# 5G8_fpv_tx.net
KiCad netlist of a schematic drawn in EAGLE
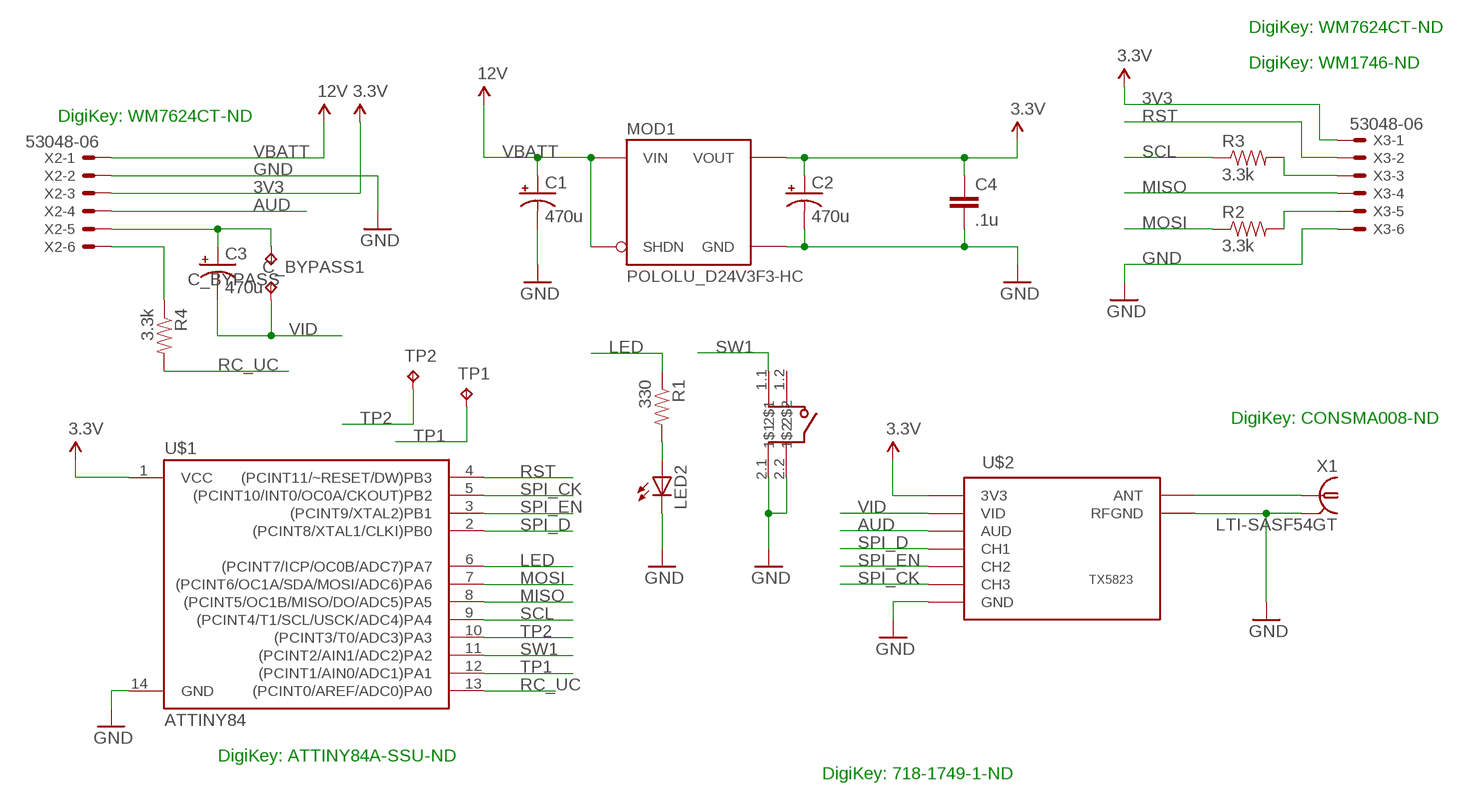
[diagram p0: schematic, sheet 1]

(export (version "E")
  (design (tool "Eeschema 10.0.6"))
  (components
    (comp (ref "C1")
      (value "470u")
      (footprint "eagle-import:VISHAY_D")
      (libsource (lib "eagle-import") (part "VISHAY_D"))
    )
    (comp (ref "C2")
      (value "470u")
      (footprint "eagle-import:VISHAY_D")
      (libsource (lib "eagle-import") (part "VISHAY_D"))
    )
    (comp (ref "C3")
      (value "470u")
      (footprint "eagle-import:VISHAY_D")
      (libsource (lib "eagle-import") (part "VISHAY_D"))
    )
    (comp (ref "C4")
      (value ".1u")
      (footprint "eagle-import:0805")
      (libsource (lib "eagle-import") (part "CAP0805"))
    )
    (comp (ref "C_BYPASS")
      (value "TPTP06SQ")
      (footprint "eagle-import:TP06SQ")
      (libsource (lib "eagle-import") (part "TPTP06SQ"))
    )
    (comp (ref "C_BYPASS1")
      (value "TPTP06SQ")
      (footprint "eagle-import:TP06SQ")
      (libsource (lib "eagle-import") (part "TPTP06SQ"))
    )
    (comp (ref "LED2")
      (value "LEDCHIPLED_0805")
      (footprint "eagle-import:CHIPLED_0805")
      (libsource (lib "eagle-import") (part "LEDCHIPLED_0805"))
    )
    (comp (ref "MOD1")
      (value "POLOLU_D24V3F3-HC")
      (footprint "eagle-import:POLOLU_D24V3F_HC")
      (libsource (lib "eagle-import") (part "POLOLU_D24V3F-HC3"))
    )
    (comp (ref "R1")
      (value "330")
      (footprint "eagle-import:0805")
      (libsource (lib "eagle-import") (part "RESISTOR0805-RES"))
    )
    (comp (ref "R2")
      (value "3.3k")
      (footprint "eagle-import:0805")
      (libsource (lib "eagle-import") (part "RESISTOR0805-RES"))
    )
    (comp (ref "R3")
      (value "3.3k")
      (footprint "eagle-import:0805")
      (libsource (lib "eagle-import") (part "RESISTOR0805-RES"))
    )
    (comp (ref "R4")
      (value "3.3k")
      (footprint "eagle-import:0805")
      (libsource (lib "eagle-import") (part "RESISTOR0805-RES"))
    )
    (comp (ref "TP1")
      (value "TPTP20SQ")
      (footprint "eagle-import:TP20SQ")
      (libsource (lib "eagle-import") (part "TPTP20SQ"))
    )
    (comp (ref "TP2")
      (value "TPTP20SQ")
      (footprint "eagle-import:TP20SQ")
      (libsource (lib "eagle-import") (part "TPTP20SQ"))
    )
    (comp (ref "U$1")
      (value "ATTINY84")
      (footprint "eagle-import:SO14")
      (libsource (lib "eagle-import") (part "ATTINY84"))
    )
    (comp (ref "U$2")
      (value "TX5823")
      (footprint "eagle-import:TX5823")
      (libsource (lib "eagle-import") (part "TX5823"))
    )
    (comp (ref "U$3")
      (value "BOURNS_7814G_SW")
      (footprint "eagle-import:7914G")
      (libsource (lib "eagle-import") (part "BOURNS_7814G_SW"))
    )
    (comp (ref "X1")
      (value "LTI-SASF54GT")
      (footprint "eagle-import:LTI-SASF54GT")
      (libsource (lib "eagle-import") (part "LTI-SASF54GT"))
    )
    (comp (ref "X2")
      (value "53048-06")
      (footprint "eagle-import:53048-06")
      (fields (field (name "MF") "WALDOM/MOLEX") (field (name "MPN") "53048-0610"))
      (libsource (lib "eagle-import") (part "53?-06048"))
    )
    (comp (ref "X3")
      (value "53048-06")
      (footprint "eagle-import:53048-06")
      (fields (field (name "MF") "WALDOM/MOLEX") (field (name "MPN") "53048-0610"))
      (libsource (lib "eagle-import") (part "53?-06048"))
    )
  )
  (nets
    (net (code "1") (name "/AUD") (class "Default")
      (node (ref "U$2") (pin "P$2") (pinfunction "AUD_P$2") (pintype "bidirectional"))
      (node (ref "X2") (pin "4") (pinfunction "S_4") (pintype "passive"))
    )
    (net (code "2") (name "/LED") (class "Default")
      (node (ref "R1") (pin "1") (pinfunction "1_1") (pintype "passive"))
      (node (ref "U$1") (pin "6") (pinfunction "(PCINT7/ICP/OC0B/ADC7)PA7_6") (pintype "bidirectional"))
    )
    (net (code "3") (name "/MISO") (class "Default")
      (node (ref "U$1") (pin "8") (pinfunction "(PCINT5/OC1B/MISO/DO/ADC5)PA5_8") (pintype "bidirectional"))
      (node (ref "X3") (pin "4") (pinfunction "S_4") (pintype "passive"))
    )
    (net (code "4") (name "/MOSI") (class "Default")
      (node (ref "R2") (pin "1") (pinfunction "1_1") (pintype "passive"))
      (node (ref "U$1") (pin "7") (pinfunction "(PCINT6/OC1A/SDA/MOSI/ADC6)PA6_7") (pintype "bidirectional"))
    )
    (net (code "5") (name "/RC_UC") (class "Default")
      (node (ref "R4") (pin "2") (pinfunction "2_2") (pintype "passive"))
      (node (ref "U$1") (pin "13") (pinfunction "(PCINT0/AREF/ADC0)PA0_13") (pintype "bidirectional"))
    )
    (net (code "6") (name "/RST") (class "Default")
      (node (ref "U$1") (pin "4") (pinfunction "(PCINT11/~{RESET/DW})PB3_4") (pintype "bidirectional"))
      (node (ref "X3") (pin "2") (pinfunction "S_2") (pintype "passive"))
    )
    (net (code "7") (name "/SCL") (class "Default")
      (node (ref "R3") (pin "1") (pinfunction "1_1") (pintype "passive"))
      (node (ref "U$1") (pin "9") (pinfunction "(PCINT4/T1/SCL/USCK/ADC4)PA4_9") (pintype "bidirectional"))
    )
    (net (code "8") (name "/SPI_CK") (class "Default")
      (node (ref "U$1") (pin "5") (pinfunction "(PCINT10/INT0/OC0A/CKOUT)PB2_5") (pintype "bidirectional"))
      (node (ref "U$2") (pin "P$8") (pinfunction "CH3_P$8") (pintype "bidirectional"))
    )
    (net (code "9") (name "/SPI_D") (class "Default")
      (node (ref "U$1") (pin "2") (pinfunction "(PCINT8/XTAL1/CLKI)PB0_2") (pintype "bidirectional"))
      (node (ref "U$2") (pin "P$6") (pinfunction "CH1_P$6") (pintype "bidirectional"))
    )
    (net (code "10") (name "/SPI_EN") (class "Default")
      (node (ref "U$1") (pin "3") (pinfunction "(PCINT9/XTAL2)PB1_3") (pintype "bidirectional"))
      (node (ref "U$2") (pin "P$7") (pinfunction "CH2_P$7") (pintype "bidirectional"))
    )
    (net (code "11") (name "/SW1") (class "Default")
      (node (ref "U$1") (pin "11") (pinfunction "(PCINT2/AIN1/ADC2)PA2_11") (pintype "bidirectional"))
      (node (ref "U$3") (pin "1.1") (pinfunction "1$1_1.1") (pintype "bidirectional"))
    )
    (net (code "12") (name "/TP1") (class "Default")
      (node (ref "TP1") (pin "TP") (pinfunction "TP_TP") (pintype "input"))
      (node (ref "U$1") (pin "12") (pinfunction "(PCINT1/AIN0/ADC1)PA1_12") (pintype "bidirectional"))
    )
    (net (code "13") (name "/TP2") (class "Default")
      (node (ref "TP2") (pin "TP") (pinfunction "TP_TP") (pintype "input"))
      (node (ref "U$1") (pin "10") (pinfunction "(PCINT3/T0/ADC3)PA3_10") (pintype "bidirectional"))
    )
    (net (code "14") (name "/VID") (class "Default")
      (node (ref "C3") (pin "-") (pinfunction "-_-") (pintype "passive"))
      (node (ref "C_BYPASS1") (pin "TP") (pinfunction "TP_TP") (pintype "input"))
      (node (ref "U$2") (pin "P$1") (pinfunction "VID_P$1") (pintype "bidirectional"))
    )
    (net (code "15") (name "3.3V") (class "Default")
      (node (ref "C2") (pin "+") (pinfunction "+_+") (pintype "passive"))
      (node (ref "C4") (pin "1") (pinfunction "1_1") (pintype "passive"))
      (node (ref "MOD1") (pin "O") (pinfunction "VOUT_O") (pintype "output"))
      (node (ref "U$1") (pin "1") (pinfunction "VCC_1") (pintype "bidirectional"))
      (node (ref "U$2") (pin "P$4") (pinfunction "3V3_P$4") (pintype "bidirectional"))
      (node (ref "X2") (pin "3") (pinfunction "S_3") (pintype "passive"))
      (node (ref "X3") (pin "1") (pinfunction "S_1") (pintype "passive"))
    )
    (net (code "16") (name "12V") (class "Default")
      (node (ref "C1") (pin "+") (pinfunction "+_+") (pintype "passive"))
      (node (ref "MOD1") (pin "I") (pinfunction "VIN_I") (pintype "power_in"))
      (node (ref "MOD1") (pin "S") (pinfunction "SHDN_S") (pintype "input"))
      (node (ref "X2") (pin "1") (pinfunction "S_1") (pintype "passive"))
    )
    (net (code "17") (name "GND") (class "Default")
      (node (ref "C1") (pin "-") (pinfunction "-_-") (pintype "passive"))
      (node (ref "C2") (pin "-") (pinfunction "-_-") (pintype "passive"))
      (node (ref "C4") (pin "2") (pinfunction "2_2") (pintype "passive"))
      (node (ref "LED2") (pin "C") (pinfunction "C_C") (pintype "passive"))
      (node (ref "MOD1") (pin "G") (pinfunction "GND_G") (pintype "power_in"))
      (node (ref "U$1") (pin "14") (pinfunction "GND_14") (pintype "bidirectional"))
      (node (ref "U$2") (pin "P$11") (pinfunction "RFGND_P$11") (pintype "bidirectional"))
      (node (ref "U$2") (pin "P$3") (pinfunction "GND_P$3") (pintype "bidirectional"))
      (node (ref "U$2") (pin "P$5") (pinfunction "GND_P$5") (pintype "bidirectional"))
      (node (ref "U$2") (pin "P$9") (pinfunction "RFGND_P$9") (pintype "bidirectional"))
      (node (ref "U$3") (pin "2.1") (pinfunction "2$1_2.1") (pintype "bidirectional"))
      (node (ref "U$3") (pin "2.2") (pinfunction "2$2_2.2") (pintype "bidirectional"))
      (node (ref "X1") (pin "2") (pinfunction "2_2") (pintype "passive"))
      (node (ref "X1") (pin "3") (pinfunction "2_3") (pintype "passive"))
      (node (ref "X1") (pin "4") (pinfunction "2_4") (pintype "passive"))
      (node (ref "X1") (pin "5") (pinfunction "2_5") (pintype "passive"))
      (node (ref "X2") (pin "2") (pinfunction "S_2") (pintype "passive"))
      (node (ref "X3") (pin "6") (pinfunction "S_6") (pintype "passive"))
    )
    (net (code "18") (name "Net-(LED2-PadA)") (class "Default")
      (node (ref "LED2") (pin "A") (pinfunction "A_A") (pintype "passive"))
      (node (ref "R1") (pin "2") (pinfunction "2_2") (pintype "passive"))
    )
    (net (code "19") (name "Net-(U$2-ANT)") (class "Default")
      (node (ref "U$2") (pin "P$10") (pinfunction "ANT_P$10") (pintype "bidirectional"))
      (node (ref "X1") (pin "1") (pinfunction "1_1") (pintype "passive"))
    )
    (net (code "20") (name "Net-(X2E-S)") (class "Default")
      (node (ref "C3") (pin "+") (pinfunction "+_+") (pintype "passive"))
      (node (ref "C_BYPASS") (pin "TP") (pinfunction "TP_TP") (pintype "input"))
      (node (ref "X2") (pin "5") (pinfunction "S_5") (pintype "passive"))
    )
    (net (code "21") (name "Net-(X2F-S)") (class "Default")
      (node (ref "R4") (pin "1") (pinfunction "1_1") (pintype "passive"))
      (node (ref "X2") (pin "6") (pinfunction "S_6") (pintype "passive"))
    )
    (net (code "22") (name "Net-(X3C-S)") (class "Default")
      (node (ref "R3") (pin "2") (pinfunction "2_2") (pintype "passive"))
      (node (ref "X3") (pin "3") (pinfunction "S_3") (pintype "passive"))
    )
    (net (code "23") (name "Net-(X3E-S)") (class "Default")
      (node (ref "R2") (pin "2") (pinfunction "2_2") (pintype "passive"))
      (node (ref "X3") (pin "5") (pinfunction "S_5") (pintype "passive"))
    )
    (net (code "24") (name "unconnected-(U$3-1$2-Pad1.2)") (class "Default")
      (node (ref "U$3") (pin "1.2") (pinfunction "1$2_1.2") (pintype "bidirectional"))
    )
  )
)
